# mcu_teensy4_1.net
KiCad netlist of a schematic drawn in EAGLE
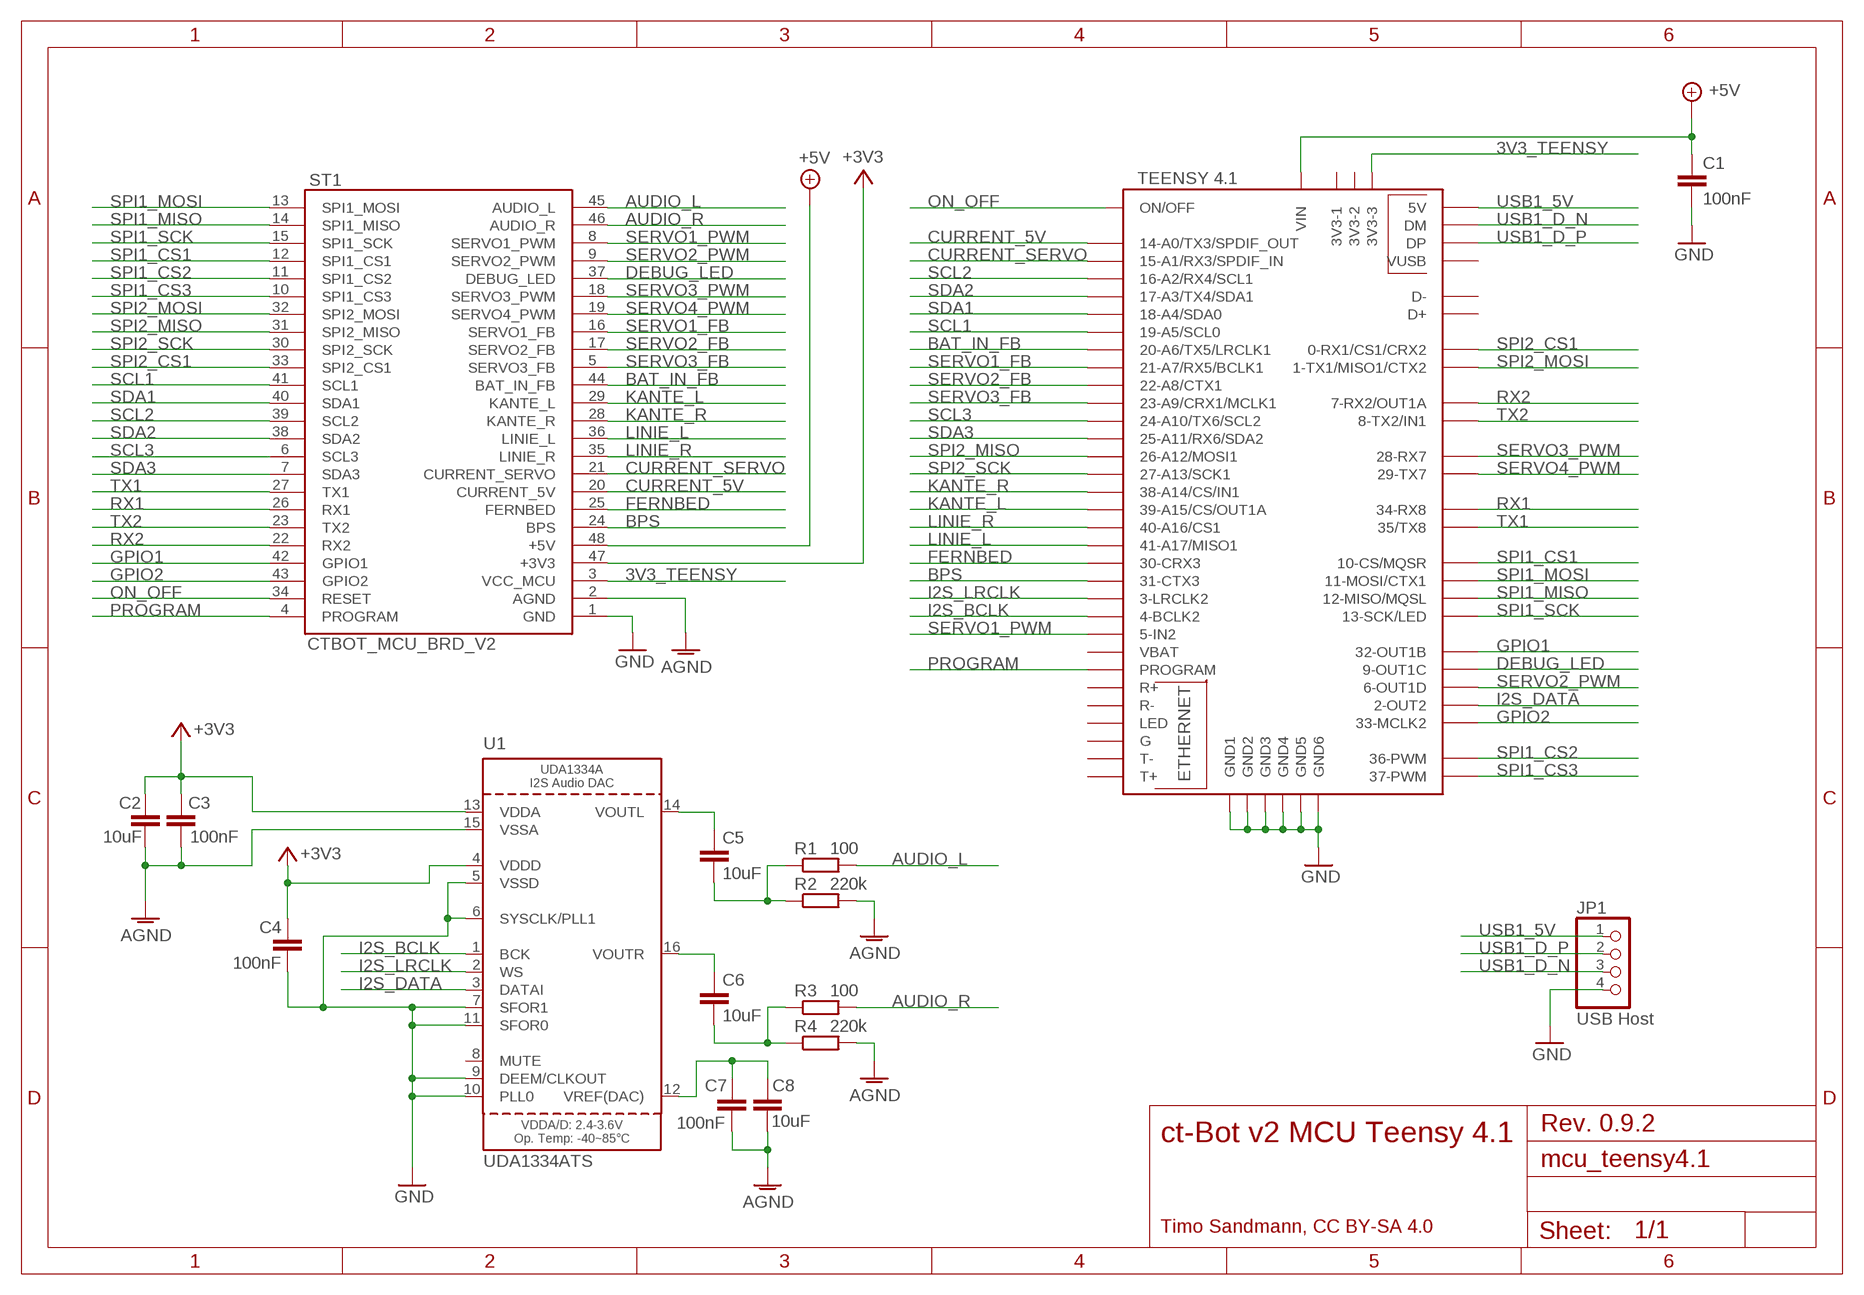
[diagram p0: schematic, sheet 1]

(export (version "E")
  (design (tool "Eeschema 10.0.6"))
  (components
    (comp (ref "C1")
      (value "100nF")
      (footprint "eagle-import:C0805")
      (libsource (lib "eagle-import") (part "C-EUC0805"))
    )
    (comp (ref "C2")
      (value "10uF")
      (footprint "eagle-import:C0805")
      (libsource (lib "eagle-import") (part "C-EUC0805"))
    )
    (comp (ref "C3")
      (value "100nF")
      (footprint "eagle-import:C0805")
      (libsource (lib "eagle-import") (part "C-EUC0805"))
    )
    (comp (ref "C4")
      (value "100nF")
      (footprint "eagle-import:C0805")
      (libsource (lib "eagle-import") (part "C-EUC0805"))
    )
    (comp (ref "C5")
      (value "10uF")
      (footprint "eagle-import:C0805")
      (libsource (lib "eagle-import") (part "C-EUC0805"))
    )
    (comp (ref "C6")
      (value "10uF")
      (footprint "eagle-import:C0805")
      (libsource (lib "eagle-import") (part "C-EUC0805"))
    )
    (comp (ref "C7")
      (value "100nF")
      (footprint "eagle-import:C0805")
      (libsource (lib "eagle-import") (part "C-EUC0805"))
    )
    (comp (ref "C8")
      (value "10uF")
      (footprint "eagle-import:C0805")
      (libsource (lib "eagle-import") (part "C-EUC0805"))
    )
    (comp (ref "JP1")
      (value "USB Host")
      (footprint "eagle-import:1X04_90")
      (libsource (lib "eagle-import") (part "PINHD-1X4/90"))
    )
    (comp (ref "R1")
      (value "100")
      (footprint "eagle-import:R0805")
      (libsource (lib "eagle-import") (part "R-EU_R0805"))
    )
    (comp (ref "R2")
      (value "220k")
      (footprint "eagle-import:R0805")
      (libsource (lib "eagle-import") (part "R-EU_R0805"))
    )
    (comp (ref "R3")
      (value "100")
      (footprint "eagle-import:R0805")
      (libsource (lib "eagle-import") (part "R-EU_R0805"))
    )
    (comp (ref "R4")
      (value "220k")
      (footprint "eagle-import:R0805")
      (libsource (lib "eagle-import") (part "R-EU_R0805"))
    )
    (comp (ref "ST1")
      (value "CTBOT_MCU_BRD_V2")
      (footprint "eagle-import:DIP48")
      (libsource (lib "eagle-import") (part "CTBOT_MCU_BRD_V2"))
    )
    (comp (ref "U$1")
      (value "TEENSY41")
      (footprint "eagle-import:TEENSY41")
      (libsource (lib "eagle-import") (part "TEENSY41"))
    )
    (comp (ref "U1")
      (value "UDA1334ATS")
      (footprint "eagle-import:SSOP16_4.4MM")
      (libsource (lib "eagle-import") (part "AUDIO_I2S_UDA1334{dblquote}{dblquote}"))
    )
  )
  (nets
    (net (code "1") (name "+3V3") (class "Default")
      (node (ref "C2") (pin "1") (pinfunction "1_1") (pintype "passive"))
      (node (ref "C3") (pin "2") (pinfunction "2_2") (pintype "passive"))
      (node (ref "C4") (pin "2") (pinfunction "2_2") (pintype "passive"))
      (node (ref "ST1") (pin "47") (pinfunction "+3V3_47") (pintype "power_in"))
      (node (ref "U1") (pin "13") (pinfunction "VDDA_13") (pintype "power_in"))
      (node (ref "U1") (pin "4") (pinfunction "VDDD_4") (pintype "power_in"))
    )
    (net (code "2") (name "+5V") (class "Default")
      (node (ref "C1") (pin "1") (pinfunction "1_1") (pintype "passive"))
      (node (ref "ST1") (pin "48") (pinfunction "+5V_48") (pintype "power_in"))
      (node (ref "U$1") (pin "VIN") (pinfunction "VIN_VIN") (pintype "bidirectional"))
    )
    (net (code "3") (name "/3V3_TEENSY") (class "Default")
      (node (ref "ST1") (pin "3") (pinfunction "VCC_MCU_3") (pintype "power_in"))
      (node (ref "U$1") (pin "3V3-3") (pinfunction "3V3-3_3V3-3") (pintype "bidirectional"))
    )
    (net (code "4") (name "/AUDIO_L") (class "Default")
      (node (ref "R1") (pin "2") (pinfunction "2_2") (pintype "passive"))
      (node (ref "ST1") (pin "45") (pinfunction "AUDIO_L_45") (pintype "output"))
    )
    (net (code "5") (name "/AUDIO_R") (class "Default")
      (node (ref "R3") (pin "2") (pinfunction "2_2") (pintype "passive"))
      (node (ref "ST1") (pin "46") (pinfunction "AUDIO_R_46") (pintype "output"))
    )
    (net (code "6") (name "/BAT_IN_FB") (class "Default")
      (node (ref "ST1") (pin "44") (pinfunction "BAT_IN_FB_44") (pintype "input"))
      (node (ref "U$1") (pin "20-A6/TX5/LRCLK1") (pinfunction "20-A6/TX5/LRCLK1_20-A6/TX5/LRCLK1") (pintype "bidirectional"))
    )
    (net (code "7") (name "/BPS") (class "Default")
      (node (ref "ST1") (pin "24") (pinfunction "BPS_24") (pintype "input"))
      (node (ref "U$1") (pin "31-CTX3") (pinfunction "31-CTX3_31-CTX3") (pintype "bidirectional"))
    )
    (net (code "8") (name "/CURRENT_5V") (class "Default")
      (node (ref "ST1") (pin "20") (pinfunction "CURRENT_5V_20") (pintype "input"))
      (node (ref "U$1") (pin "14-A0/TX3/SPDIF_OUT") (pinfunction "14-A0/TX3/SPDIF_OUT_14-A0/TX3/SPDIF_OUT") (pintype "bidirectional"))
    )
    (net (code "9") (name "/CURRENT_SERVO") (class "Default")
      (node (ref "ST1") (pin "21") (pinfunction "CURRENT_SERVO_21") (pintype "input"))
      (node (ref "U$1") (pin "15-A1/RX3/SPDIF_IN") (pinfunction "15-A1/RX3/SPDIF_IN_15-A1/RX3/SPDIF_IN") (pintype "bidirectional"))
    )
    (net (code "10") (name "/DEBUG_LED") (class "Default")
      (node (ref "ST1") (pin "37") (pinfunction "DEBUG_LED_37") (pintype "output"))
      (node (ref "U$1") (pin "9-OUT1C") (pinfunction "9-OUT1C_9-OUT1C") (pintype "bidirectional"))
    )
    (net (code "11") (name "/FERNBED") (class "Default")
      (node (ref "ST1") (pin "25") (pinfunction "FERNBED_25") (pintype "input"))
      (node (ref "U$1") (pin "30-CRX3") (pinfunction "30-CRX3_30-CRX3") (pintype "bidirectional"))
    )
    (net (code "12") (name "/GPIO1") (class "Default")
      (node (ref "ST1") (pin "42") (pinfunction "GPIO1_42") (pintype "bidirectional"))
      (node (ref "U$1") (pin "32-OUT1B") (pinfunction "32-OUT1B_32-OUT1B") (pintype "bidirectional"))
    )
    (net (code "13") (name "/GPIO2") (class "Default")
      (node (ref "ST1") (pin "43") (pinfunction "GPIO2_43") (pintype "bidirectional"))
      (node (ref "U$1") (pin "33-MCLK2") (pinfunction "33-MCLK2_33-MCLK2") (pintype "bidirectional"))
    )
    (net (code "14") (name "/I2S_BCLK") (class "Default")
      (node (ref "U$1") (pin "4-BCLK2") (pinfunction "4-BCLK2_4-BCLK2") (pintype "bidirectional"))
      (node (ref "U1") (pin "1") (pinfunction "BCK_1") (pintype "input"))
    )
    (net (code "15") (name "/I2S_DATA") (class "Default")
      (node (ref "U$1") (pin "2-OUT2") (pinfunction "2-OUT2_2-OUT2") (pintype "bidirectional"))
      (node (ref "U1") (pin "3") (pinfunction "DATAI_3") (pintype "input"))
    )
    (net (code "16") (name "/I2S_LRCLK") (class "Default")
      (node (ref "U$1") (pin "3-LRCLK2") (pinfunction "3-LRCLK2_3-LRCLK2") (pintype "bidirectional"))
      (node (ref "U1") (pin "2") (pinfunction "WS_2") (pintype "input"))
    )
    (net (code "17") (name "/KANTE_L") (class "Default")
      (node (ref "ST1") (pin "29") (pinfunction "KANTE_L_29") (pintype "input"))
      (node (ref "U$1") (pin "39-A15/CS/OUT1A") (pinfunction "39-A15/CS/OUT1A_39-A15/CS/OUT1A") (pintype "bidirectional"))
    )
    (net (code "18") (name "/KANTE_R") (class "Default")
      (node (ref "ST1") (pin "28") (pinfunction "KANTE_R_28") (pintype "input"))
      (node (ref "U$1") (pin "38-A14/CS/IN1") (pinfunction "38-A14/CS/IN1_38-A14/CS/IN1") (pintype "bidirectional"))
    )
    (net (code "19") (name "/LINIE_L") (class "Default")
      (node (ref "ST1") (pin "36") (pinfunction "LINIE_L_36") (pintype "input"))
      (node (ref "U$1") (pin "41-A17/MISO1") (pinfunction "41-A17/MISO1_41-A17/MISO1") (pintype "bidirectional"))
    )
    (net (code "20") (name "/LINIE_R") (class "Default")
      (node (ref "ST1") (pin "35") (pinfunction "LINIE_R_35") (pintype "input"))
      (node (ref "U$1") (pin "40-A16/CS1") (pinfunction "40-A16/CS1_40-A16/CS1") (pintype "bidirectional"))
    )
    (net (code "21") (name "/ON_OFF") (class "Default")
      (node (ref "ST1") (pin "34") (pinfunction "RESET_34") (pintype "input"))
      (node (ref "U$1") (pin "ON/OFF") (pinfunction "ON/OFF_ON/OFF") (pintype "bidirectional"))
    )
    (net (code "22") (name "/PROGRAM") (class "Default")
      (node (ref "ST1") (pin "4") (pinfunction "PROGRAM_4") (pintype "input"))
      (node (ref "U$1") (pin "PROGRAM") (pinfunction "PROGRAM_PROGRAM") (pintype "bidirectional"))
    )
    (net (code "23") (name "/RX1") (class "Default")
      (node (ref "ST1") (pin "26") (pinfunction "RX1_26") (pintype "input"))
      (node (ref "U$1") (pin "34-RX8") (pinfunction "34-RX8_34-RX8") (pintype "bidirectional"))
    )
    (net (code "24") (name "/RX2") (class "Default")
      (node (ref "ST1") (pin "22") (pinfunction "RX2_22") (pintype "input"))
      (node (ref "U$1") (pin "7-RX2/OUT1A") (pinfunction "7-RX2/OUT1A_7-RX2/OUT1A") (pintype "bidirectional"))
    )
    (net (code "25") (name "/SCL1") (class "Default")
      (node (ref "ST1") (pin "41") (pinfunction "SCL1_41") (pintype "output"))
      (node (ref "U$1") (pin "19-A5/SCL0") (pinfunction "19-A5/SCL0_19-A5/SCL0") (pintype "bidirectional"))
    )
    (net (code "26") (name "/SCL2") (class "Default")
      (node (ref "ST1") (pin "39") (pinfunction "SCL2_39") (pintype "output"))
      (node (ref "U$1") (pin "16-A2/RX4/SCL1") (pinfunction "16-A2/RX4/SCL1_16-A2/RX4/SCL1") (pintype "bidirectional"))
    )
    (net (code "27") (name "/SCL3") (class "Default")
      (node (ref "ST1") (pin "6") (pinfunction "SCL3_6") (pintype "output"))
      (node (ref "U$1") (pin "24-A10/TX6/SCL2") (pinfunction "24-A10/TX6/SCL2_24-A10/TX6/SCL2") (pintype "bidirectional"))
    )
    (net (code "28") (name "/SDA1") (class "Default")
      (node (ref "ST1") (pin "40") (pinfunction "SDA1_40") (pintype "bidirectional"))
      (node (ref "U$1") (pin "18-A4/SDA0") (pinfunction "18-A4/SDA0_18-A4/SDA0") (pintype "bidirectional"))
    )
    (net (code "29") (name "/SDA2") (class "Default")
      (node (ref "ST1") (pin "38") (pinfunction "SDA2_38") (pintype "bidirectional"))
      (node (ref "U$1") (pin "17-A3/TX4/SDA1") (pinfunction "17-A3/TX4/SDA1_17-A3/TX4/SDA1") (pintype "bidirectional"))
    )
    (net (code "30") (name "/SDA3") (class "Default")
      (node (ref "ST1") (pin "7") (pinfunction "SDA3_7") (pintype "bidirectional"))
      (node (ref "U$1") (pin "25-A11/RX6/SDA2") (pinfunction "25-A11/RX6/SDA2_25-A11/RX6/SDA2") (pintype "bidirectional"))
    )
    (net (code "31") (name "/SERVO1_FB") (class "Default")
      (node (ref "ST1") (pin "16") (pinfunction "SERVO1_FB_16") (pintype "input"))
      (node (ref "U$1") (pin "21-A7/RX5/BCLK1") (pinfunction "21-A7/RX5/BCLK1_21-A7/RX5/BCLK1") (pintype "bidirectional"))
    )
    (net (code "32") (name "/SERVO1_PWM") (class "Default")
      (node (ref "ST1") (pin "8") (pinfunction "SERVO1_PWM_8") (pintype "output"))
      (node (ref "U$1") (pin "5-IN2") (pinfunction "5-IN2_5-IN2") (pintype "bidirectional"))
    )
    (net (code "33") (name "/SERVO2_FB") (class "Default")
      (node (ref "ST1") (pin "17") (pinfunction "SERVO2_FB_17") (pintype "input"))
      (node (ref "U$1") (pin "22-A8/CTX1") (pinfunction "22-A8/CTX1_22-A8/CTX1") (pintype "bidirectional"))
    )
    (net (code "34") (name "/SERVO2_PWM") (class "Default")
      (node (ref "ST1") (pin "9") (pinfunction "SERVO2_PWM_9") (pintype "output"))
      (node (ref "U$1") (pin "6-OUT1D") (pinfunction "6-OUT1D_6-OUT1D") (pintype "bidirectional"))
    )
    (net (code "35") (name "/SERVO3_FB") (class "Default")
      (node (ref "ST1") (pin "5") (pinfunction "SERVO3_FB_5") (pintype "input"))
      (node (ref "U$1") (pin "23-A9/CRX1/MCLK1") (pinfunction "23-A9/CRX1/MCLK1_23-A9/CRX1/MCLK1") (pintype "bidirectional"))
    )
    (net (code "36") (name "/SERVO3_PWM") (class "Default")
      (node (ref "ST1") (pin "18") (pinfunction "SERVO3_PWM_18") (pintype "bidirectional"))
      (node (ref "U$1") (pin "28-RX7") (pinfunction "28-RX7_28-RX7") (pintype "bidirectional"))
    )
    (net (code "37") (name "/SERVO4_PWM") (class "Default")
      (node (ref "ST1") (pin "19") (pinfunction "SERVO4_PWM_19") (pintype "bidirectional"))
      (node (ref "U$1") (pin "29-TX7") (pinfunction "29-TX7_29-TX7") (pintype "bidirectional"))
    )
    (net (code "38") (name "/SPI1_CS1") (class "Default")
      (node (ref "ST1") (pin "12") (pinfunction "SPI1_CS1_12") (pintype "output"))
      (node (ref "U$1") (pin "10-CS\\MQSR") (pinfunction "10-CS/MQSR_10-CS\\MQSR") (pintype "bidirectional"))
    )
    (net (code "39") (name "/SPI1_CS2") (class "Default")
      (node (ref "ST1") (pin "11") (pinfunction "SPI1_CS2_11") (pintype "output"))
      (node (ref "U$1") (pin "36-PWM") (pinfunction "36-PWM_36-PWM") (pintype "bidirectional"))
    )
    (net (code "40") (name "/SPI1_CS3") (class "Default")
      (node (ref "ST1") (pin "10") (pinfunction "SPI1_CS3_10") (pintype "output"))
      (node (ref "U$1") (pin "37-PWM") (pinfunction "37-PWM_37-PWM") (pintype "bidirectional"))
    )
    (net (code "41") (name "/SPI1_MISO") (class "Default")
      (node (ref "ST1") (pin "14") (pinfunction "SPI1_MISO_14") (pintype "input"))
      (node (ref "U$1") (pin "12-MISO/MQSL") (pinfunction "12-MISO/MQSL_12-MISO/MQSL") (pintype "bidirectional"))
    )
    (net (code "42") (name "/SPI1_MOSI") (class "Default")
      (node (ref "ST1") (pin "13") (pinfunction "SPI1_MOSI_13") (pintype "output"))
      (node (ref "U$1") (pin "11-MOSI/CTX1") (pinfunction "11-MOSI/CTX1_11-MOSI/CTX1") (pintype "bidirectional"))
    )
    (net (code "43") (name "/SPI1_SCK") (class "Default")
      (node (ref "ST1") (pin "15") (pinfunction "SPI1_SCK_15") (pintype "output"))
      (node (ref "U$1") (pin "13-SCK/LED") (pinfunction "13-SCK/LED_13-SCK/LED") (pintype "bidirectional"))
    )
    (net (code "44") (name "/SPI2_CS1") (class "Default")
      (node (ref "ST1") (pin "33") (pinfunction "SPI2_CS1_33") (pintype "output"))
      (node (ref "U$1") (pin "0-RX1/CS1/CRX2") (pinfunction "0-RX1/CS1/CRX2_0-RX1/CS1/CRX2") (pintype "bidirectional"))
    )
    (net (code "45") (name "/SPI2_MISO") (class "Default")
      (node (ref "ST1") (pin "31") (pinfunction "SPI2_MISO_31") (pintype "input"))
      (node (ref "U$1") (pin "26-A12/MOSI1") (pinfunction "26-A12/MOSI1_26-A12/MOSI1") (pintype "bidirectional"))
    )
    (net (code "46") (name "/SPI2_MOSI") (class "Default")
      (node (ref "ST1") (pin "32") (pinfunction "SPI2_MOSI_32") (pintype "output"))
      (node (ref "U$1") (pin "1-TX1/MISO1/CTX2") (pinfunction "1-TX1/MISO1/CTX2_1-TX1/MISO1/CTX2") (pintype "bidirectional"))
    )
    (net (code "47") (name "/SPI2_SCK") (class "Default")
      (node (ref "ST1") (pin "30") (pinfunction "SPI2_SCK_30") (pintype "output"))
      (node (ref "U$1") (pin "27-A13/SCK1") (pinfunction "27-A13/SCK1_27-A13/SCK1") (pintype "bidirectional"))
    )
    (net (code "48") (name "/TX1") (class "Default")
      (node (ref "ST1") (pin "27") (pinfunction "TX1_27") (pintype "output"))
      (node (ref "U$1") (pin "35-TX8") (pinfunction "35/TX8_35-TX8") (pintype "bidirectional"))
    )
    (net (code "49") (name "/TX2") (class "Default")
      (node (ref "ST1") (pin "23") (pinfunction "TX2_23") (pintype "output"))
      (node (ref "U$1") (pin "8-TX2/IN1") (pinfunction "8-TX2/IN1_8-TX2/IN1") (pintype "bidirectional"))
    )
    (net (code "50") (name "/USB1_5V") (class "Default")
      (node (ref "JP1") (pin "1") (pinfunction "1_1") (pintype "passive"))
      (node (ref "U$1") (pin "+5V") (pinfunction "5V_+5V") (pintype "bidirectional"))
    )
    (net (code "51") (name "/USB1_D_N") (class "Default")
      (node (ref "JP1") (pin "3") (pinfunction "3_3") (pintype "passive"))
      (node (ref "U$1") (pin "DM") (pinfunction "DM_DM") (pintype "bidirectional"))
    )
    (net (code "52") (name "/USB1_D_P") (class "Default")
      (node (ref "JP1") (pin "2") (pinfunction "2_2") (pintype "passive"))
      (node (ref "U$1") (pin "DP") (pinfunction "DP_DP") (pintype "bidirectional"))
    )
    (net (code "53") (name "AGND") (class "Default")
      (node (ref "C2") (pin "2") (pinfunction "2_2") (pintype "passive"))
      (node (ref "C3") (pin "1") (pinfunction "1_1") (pintype "passive"))
      (node (ref "C7") (pin "1") (pinfunction "1_1") (pintype "passive"))
      (node (ref "C8") (pin "1") (pinfunction "1_1") (pintype "passive"))
      (node (ref "R2") (pin "2") (pinfunction "2_2") (pintype "passive"))
      (node (ref "R4") (pin "2") (pinfunction "2_2") (pintype "passive"))
      (node (ref "ST1") (pin "2") (pinfunction "AGND_2") (pintype "power_in"))
      (node (ref "U1") (pin "15") (pinfunction "VSSA_15") (pintype "power_in"))
    )
    (net (code "54") (name "GND") (class "Default")
      (node (ref "C1") (pin "2") (pinfunction "2_2") (pintype "passive"))
      (node (ref "C4") (pin "1") (pinfunction "1_1") (pintype "passive"))
      (node (ref "JP1") (pin "4") (pinfunction "4_4") (pintype "passive"))
      (node (ref "ST1") (pin "1") (pinfunction "GND_1") (pintype "power_in"))
      (node (ref "U$1") (pin "GND1") (pinfunction "GND1_GND1") (pintype "bidirectional"))
      (node (ref "U$1") (pin "GND2") (pinfunction "GND2_GND2") (pintype "bidirectional"))
      (node (ref "U$1") (pin "GND3") (pinfunction "GND3_GND3") (pintype "bidirectional"))
      (node (ref "U$1") (pin "GND4") (pinfunction "GND4_GND4") (pintype "bidirectional"))
      (node (ref "U$1") (pin "GND5") (pinfunction "GND5_GND5") (pintype "bidirectional"))
      (node (ref "U$1") (pin "GND6") (pinfunction "GND6_GND6") (pintype "bidirectional"))
      (node (ref "U1") (pin "10") (pinfunction "PLL0_10") (pintype "input"))
      (node (ref "U1") (pin "11") (pinfunction "SFOR0_11") (pintype "input"))
      (node (ref "U1") (pin "5") (pinfunction "VSSD_5") (pintype "power_in"))
      (node (ref "U1") (pin "6") (pinfunction "SYSCLK/PLL1_6") (pintype "input"))
      (node (ref "U1") (pin "7") (pinfunction "SFOR1_7") (pintype "input"))
      (node (ref "U1") (pin "9") (pinfunction "DEEM/CLKOUT_9") (pintype "bidirectional"))
    )
    (net (code "55") (name "Net-(C5-Pad2)") (class "Default")
      (node (ref "C5") (pin "2") (pinfunction "2_2") (pintype "passive"))
      (node (ref "R1") (pin "1") (pinfunction "1_1") (pintype "passive"))
      (node (ref "R2") (pin "1") (pinfunction "1_1") (pintype "passive"))
    )
    (net (code "56") (name "Net-(C6-Pad2)") (class "Default")
      (node (ref "C6") (pin "2") (pinfunction "2_2") (pintype "passive"))
      (node (ref "R3") (pin "1") (pinfunction "1_1") (pintype "passive"))
      (node (ref "R4") (pin "1") (pinfunction "1_1") (pintype "passive"))
    )
    (net (code "57") (name "Net-(U1-VOUTL)") (class "Default")
      (node (ref "C5") (pin "1") (pinfunction "1_1") (pintype "passive"))
      (node (ref "U1") (pin "14") (pinfunction "VOUTL_14") (pintype "output"))
    )
    (net (code "58") (name "Net-(U1-VOUTR)") (class "Default")
      (node (ref "C6") (pin "1") (pinfunction "1_1") (pintype "passive"))
      (node (ref "U1") (pin "16") (pinfunction "VOUTR_16") (pintype "output"))
    )
    (net (code "59") (name "Net-(U1-VREF(DAC))") (class "Default")
      (node (ref "C7") (pin "2") (pinfunction "2_2") (pintype "passive"))
      (node (ref "C8") (pin "2") (pinfunction "2_2") (pintype "passive"))
      (node (ref "U1") (pin "12") (pinfunction "VREF(DAC)_12") (pintype "output"))
    )
    (net (code "60") (name "unconnected-(U$1-Pad3V3-1)") (class "Default")
      (node (ref "U$1") (pin "3V3-1") (pinfunction "3V3-1_3V3-1") (pintype "bidirectional"))
    )
    (net (code "61") (name "unconnected-(U$1-Pad3V3-2)") (class "Default")
      (node (ref "U$1") (pin "3V3-2") (pinfunction "3V3-2_3V3-2") (pintype "bidirectional"))
    )
    (net (code "62") (name "unconnected-(U$1-PadD+)") (class "Default")
      (node (ref "U$1") (pin "D+") (pinfunction "D+_D+") (pintype "bidirectional"))
    )
    (net (code "63") (name "unconnected-(U$1-PadD-)") (class "Default")
      (node (ref "U$1") (pin "D-") (pinfunction "D-_D-") (pintype "bidirectional"))
    )
    (net (code "64") (name "unconnected-(U$1-PadG)") (class "Default")
      (node (ref "U$1") (pin "G") (pinfunction "G_G") (pintype "bidirectional"))
    )
    (net (code "65") (name "unconnected-(U$1-PadLED)") (class "Default")
      (node (ref "U$1") (pin "LED") (pinfunction "LED_LED") (pintype "bidirectional"))
    )
    (net (code "66") (name "unconnected-(U$1-PadR+)") (class "Default")
      (node (ref "U$1") (pin "R+") (pinfunction "R+_R+") (pintype "bidirectional"))
    )
    (net (code "67") (name "unconnected-(U$1-PadR-)") (class "Default")
      (node (ref "U$1") (pin "R-") (pinfunction "R-_R-") (pintype "bidirectional"))
    )
    (net (code "68") (name "unconnected-(U$1-PadT+)") (class "Default")
      (node (ref "U$1") (pin "T+") (pinfunction "T+_T+") (pintype "bidirectional"))
    )
    (net (code "69") (name "unconnected-(U$1-PadT-)") (class "Default")
      (node (ref "U$1") (pin "T-") (pinfunction "T-_T-") (pintype "bidirectional"))
    )
    (net (code "70") (name "unconnected-(U$1-PadVBAT)") (class "Default")
      (node (ref "U$1") (pin "VBAT") (pinfunction "VBAT_VBAT") (pintype "bidirectional"))
    )
    (net (code "71") (name "unconnected-(U$1-PadVUSB)") (class "Default")
      (node (ref "U$1") (pin "VUSB") (pinfunction "VUSB_VUSB") (pintype "bidirectional"))
    )
    (net (code "72") (name "unconnected-(U1-MUTE-Pad8)") (class "Default")
      (node (ref "U1") (pin "8") (pinfunction "MUTE_8") (pintype "input"))
    )
  )
)
